# hex.net
KiCad netlist of a schematic drawn in Altium Designer
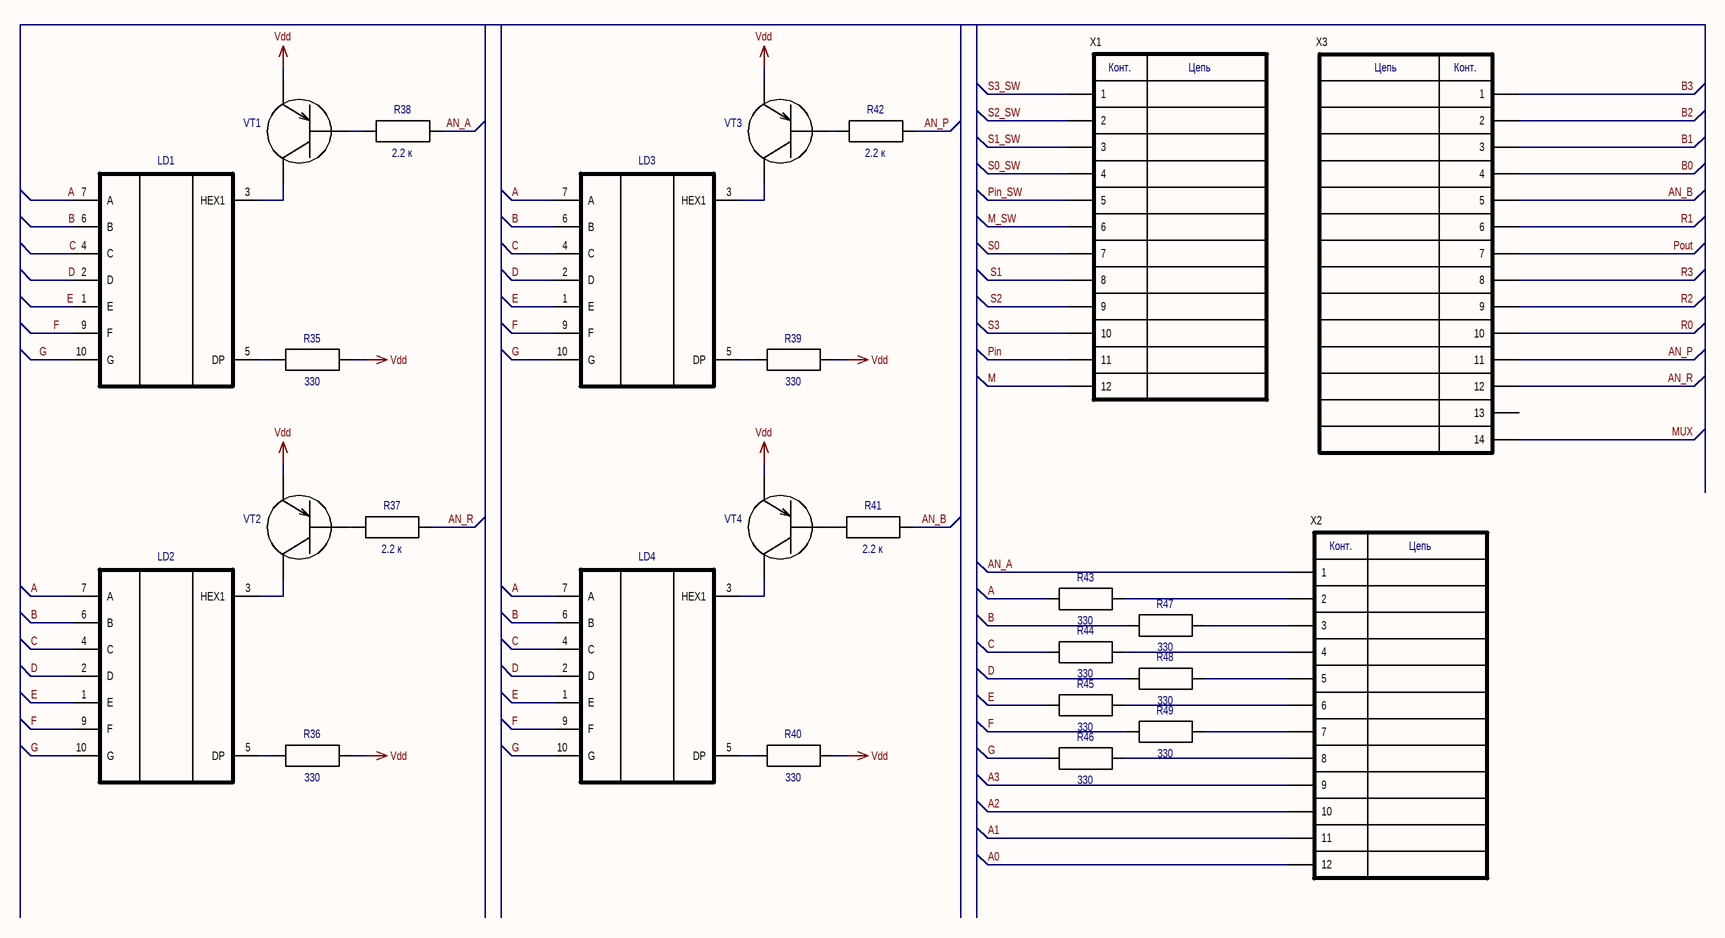
[diagram p0: hex.SchDoc]

(export (version "E")
  (design (tool "Eeschema 10.0.6"))
  (components
    (comp (ref "LD1")
      (value "4042AS (TSOT-23) Linear Technology")
      (footprint "HEX")
      (fields (field (name "PARTNUMBER") "4042AS"))
      (libsource (lib "ALU") (part "7-сегментный индикатор_2_1"))
    )
    (comp (ref "LD2")
      (value "4042AS (TSOT-23) Linear Technology")
      (footprint "HEX")
      (fields (field (name "PARTNUMBER") "4042AS"))
      (libsource (lib "ALU") (part "7-сегментный индикатор_2_1"))
    )
    (comp (ref "LD3")
      (value "4042AS (TSOT-23) Linear Technology")
      (footprint "HEX")
      (fields (field (name "PARTNUMBER") "4042AS"))
      (libsource (lib "ALU") (part "7-сегментный индикатор_2_1"))
    )
    (comp (ref "LD4")
      (value "4042AS (TSOT-23) Linear Technology")
      (footprint "HEX")
      (fields (field (name "PARTNUMBER") "4042AS"))
      (libsource (lib "ALU") (part "7-сегментный индикатор_2_1"))
    )
    (comp (ref "R35")
      (value "330")
      (footprint "P1-12-0.1(0603)")
      (fields (field (name "Comment") "330Ом ±* *, *"))
      (libsource (lib "Lisaveta") (part "R"))
    )
    (comp (ref "R36")
      (value "330")
      (footprint "P1-12-0.1(0603)")
      (fields (field (name "Comment") "330Ом ±* *, *"))
      (libsource (lib "Lisaveta") (part "R"))
    )
    (comp (ref "R37")
      (value "2.2 к")
      (footprint "P1-12-0.1(0603)")
      (fields (field (name "Comment") "2.2 кОм ±* *, *"))
      (libsource (lib "Lisaveta") (part "R"))
    )
    (comp (ref "R38")
      (value "2.2 к")
      (footprint "P1-12-0.1(0603)")
      (fields (field (name "Comment") "2.2 кОм ±* *, *"))
      (libsource (lib "Lisaveta") (part "R"))
    )
    (comp (ref "R39")
      (value "330")
      (footprint "P1-12-0.1(0603)")
      (fields (field (name "Comment") "330Ом ±* *, *"))
      (libsource (lib "Lisaveta") (part "R"))
    )
    (comp (ref "R40")
      (value "330")
      (footprint "P1-12-0.1(0603)")
      (fields (field (name "Comment") "330Ом ±* *, *"))
      (libsource (lib "Lisaveta") (part "R"))
    )
    (comp (ref "R41")
      (value "2.2 к")
      (footprint "P1-12-0.1(0603)")
      (fields (field (name "Comment") "2.2 кОм ±* *, *"))
      (libsource (lib "Lisaveta") (part "R"))
    )
    (comp (ref "R42")
      (value "2.2 к")
      (footprint "P1-12-0.1(0603)")
      (fields (field (name "Comment") "2.2 кОм ±* *, *"))
      (libsource (lib "Lisaveta") (part "R"))
    )
    (comp (ref "R43")
      (value "330")
      (footprint "P1-12-0.1(0603)")
      (fields (field (name "Comment") "330Ом ±* *, *"))
      (libsource (lib "Lisaveta") (part "R"))
    )
    (comp (ref "R44")
      (value "330")
      (footprint "P1-12-0.1(0603)")
      (fields (field (name "Comment") "330Ом ±* *, *"))
      (libsource (lib "Lisaveta") (part "R"))
    )
    (comp (ref "R45")
      (value "330")
      (footprint "P1-12-0.1(0603)")
      (fields (field (name "Comment") "330Ом ±* *, *"))
      (libsource (lib "Lisaveta") (part "R"))
    )
    (comp (ref "R46")
      (value "330")
      (footprint "P1-12-0.1(0603)")
      (fields (field (name "Comment") "330Ом ±* *, *"))
      (libsource (lib "Lisaveta") (part "R"))
    )
    (comp (ref "R47")
      (value "330")
      (footprint "P1-12-0.1(0603)")
      (fields (field (name "Comment") "330Ом ±* *, *"))
      (libsource (lib "Lisaveta") (part "R"))
    )
    (comp (ref "R48")
      (value "330")
      (footprint "P1-12-0.1(0603)")
      (fields (field (name "Comment") "330Ом ±* *, *"))
      (libsource (lib "Lisaveta") (part "R"))
    )
    (comp (ref "R49")
      (value "330")
      (footprint "P1-12-0.1(0603)")
      (fields (field (name "Comment") "330Ом ±* *, *"))
      (libsource (lib "Lisaveta") (part "R"))
    )
    (comp (ref "VT1")
      (value "BC857C (SOT-23) NXP")
      (footprint "SOT23(KT-46)")
      (fields (field (name "PARTNUMBER") "BC857C"))
      (libsource (lib "IVT_LIB") (part "VT - Биполярный транзистор PNP"))
    )
    (comp (ref "VT2")
      (value "BC857C (SOT-23) NXP")
      (footprint "SOT23(KT-46)")
      (fields (field (name "PARTNUMBER") "BC857C"))
      (libsource (lib "IVT_LIB") (part "VT - Биполярный транзистор PNP"))
    )
    (comp (ref "VT3")
      (value "BC857C (SOT-23) NXP")
      (footprint "SOT23(KT-46)")
      (fields (field (name "PARTNUMBER") "BC857C"))
      (libsource (lib "IVT_LIB") (part "VT - Биполярный транзистор PNP"))
    )
    (comp (ref "VT4")
      (value "BC857C (SOT-23) NXP")
      (footprint "SOT23(KT-46)")
      (fields (field (name "PARTNUMBER") "BC857C"))
      (libsource (lib "IVT_LIB") (part "VT - Биполярный транзистор PNP"))
    )
    (comp (ref "X1") (value "12pin") (footprint "PBD-12") (libsource (lib "ALU") (part "12pin")))
    (comp (ref "X2") (value "12pin") (footprint "PBD-12") (libsource (lib "ALU") (part "12pin")))
    (comp (ref "X3") (value "14pin") (footprint "PBD-14") (libsource (lib "ALU") (part "14pin")))
  )
  (nets
    (net (code "1") (name "/A") (class "Default")
      (node (ref "LD1") (pin "7") (pinfunction "A_7") (pintype "passive"))
      (node (ref "LD2") (pin "7") (pinfunction "A_7") (pintype "passive"))
      (node (ref "LD3") (pin "7") (pinfunction "A_7") (pintype "passive"))
      (node (ref "LD4") (pin "7") (pinfunction "A_7") (pintype "passive"))
      (node (ref "R43") (pin "1") (pinfunction "1_1") (pintype "passive"))
    )
    (net (code "2") (name "/A0") (class "Default")
      (node (ref "X2") (pin "12") (pinfunction "12_12") (pintype "passive"))
    )
    (net (code "3") (name "/A1") (class "Default")
      (node (ref "X2") (pin "11") (pinfunction "11_11") (pintype "passive"))
    )
    (net (code "4") (name "/A2") (class "Default")
      (node (ref "X2") (pin "10") (pinfunction "10_10") (pintype "passive"))
    )
    (net (code "5") (name "/A3") (class "Default")
      (node (ref "X2") (pin "9") (pinfunction "9_9") (pintype "passive"))
    )
    (net (code "6") (name "/AN_A") (class "Default")
      (node (ref "R38") (pin "2") (pinfunction "2_2") (pintype "passive"))
      (node (ref "X2") (pin "1") (pinfunction "1_1") (pintype "passive"))
    )
    (net (code "7") (name "/AN_B") (class "Default")
      (node (ref "R41") (pin "2") (pinfunction "2_2") (pintype "passive"))
      (node (ref "X3") (pin "5") (pinfunction "5_5") (pintype "passive"))
    )
    (net (code "8") (name "/AN_P") (class "Default")
      (node (ref "R42") (pin "2") (pinfunction "2_2") (pintype "passive"))
      (node (ref "X3") (pin "11") (pinfunction "11_11") (pintype "passive"))
    )
    (net (code "9") (name "/AN_R") (class "Default")
      (node (ref "R37") (pin "2") (pinfunction "2_2") (pintype "passive"))
      (node (ref "X3") (pin "12") (pinfunction "12_12") (pintype "passive"))
    )
    (net (code "10") (name "/B") (class "Default")
      (node (ref "LD1") (pin "6") (pinfunction "B_6") (pintype "passive"))
      (node (ref "LD2") (pin "6") (pinfunction "B_6") (pintype "passive"))
      (node (ref "LD3") (pin "6") (pinfunction "B_6") (pintype "passive"))
      (node (ref "LD4") (pin "6") (pinfunction "B_6") (pintype "passive"))
      (node (ref "R47") (pin "1") (pinfunction "1_1") (pintype "passive"))
    )
    (net (code "11") (name "/B0") (class "Default")
      (node (ref "X3") (pin "4") (pinfunction "4_4") (pintype "passive"))
    )
    (net (code "12") (name "/B1") (class "Default")
      (node (ref "X3") (pin "3") (pinfunction "3_3") (pintype "passive"))
    )
    (net (code "13") (name "/B2") (class "Default")
      (node (ref "X3") (pin "2") (pinfunction "2_2") (pintype "passive"))
    )
    (net (code "14") (name "/B3") (class "Default")
      (node (ref "X3") (pin "1") (pinfunction "1_1") (pintype "passive"))
    )
    (net (code "15") (name "/C") (class "Default")
      (node (ref "LD1") (pin "4") (pinfunction "C_4") (pintype "passive"))
      (node (ref "LD2") (pin "4") (pinfunction "C_4") (pintype "passive"))
      (node (ref "LD3") (pin "4") (pinfunction "C_4") (pintype "passive"))
      (node (ref "LD4") (pin "4") (pinfunction "C_4") (pintype "passive"))
      (node (ref "R44") (pin "1") (pinfunction "1_1") (pintype "passive"))
    )
    (net (code "16") (name "/D") (class "Default")
      (node (ref "LD1") (pin "2") (pinfunction "D_2") (pintype "passive"))
      (node (ref "LD2") (pin "2") (pinfunction "D_2") (pintype "passive"))
      (node (ref "LD3") (pin "2") (pinfunction "D_2") (pintype "passive"))
      (node (ref "LD4") (pin "2") (pinfunction "D_2") (pintype "passive"))
      (node (ref "R48") (pin "1") (pinfunction "1_1") (pintype "passive"))
    )
    (net (code "17") (name "/E") (class "Default")
      (node (ref "LD1") (pin "1") (pinfunction "E_1") (pintype "passive"))
      (node (ref "LD2") (pin "1") (pinfunction "E_1") (pintype "passive"))
      (node (ref "LD3") (pin "1") (pinfunction "E_1") (pintype "passive"))
      (node (ref "LD4") (pin "1") (pinfunction "E_1") (pintype "passive"))
      (node (ref "R45") (pin "1") (pinfunction "1_1") (pintype "passive"))
    )
    (net (code "18") (name "/F") (class "Default")
      (node (ref "LD1") (pin "9") (pinfunction "F_9") (pintype "passive"))
      (node (ref "LD2") (pin "9") (pinfunction "F_9") (pintype "passive"))
      (node (ref "LD3") (pin "9") (pinfunction "F_9") (pintype "passive"))
      (node (ref "LD4") (pin "9") (pinfunction "F_9") (pintype "passive"))
      (node (ref "R49") (pin "1") (pinfunction "1_1") (pintype "passive"))
    )
    (net (code "19") (name "/G") (class "Default")
      (node (ref "LD1") (pin "10") (pinfunction "G_10") (pintype "passive"))
      (node (ref "LD2") (pin "10") (pinfunction "G_10") (pintype "passive"))
      (node (ref "LD3") (pin "10") (pinfunction "G_10") (pintype "passive"))
      (node (ref "LD4") (pin "10") (pinfunction "G_10") (pintype "passive"))
      (node (ref "R46") (pin "1") (pinfunction "1_1") (pintype "passive"))
    )
    (net (code "20") (name "/M") (class "Default")
      (node (ref "X1") (pin "12") (pinfunction "12_12") (pintype "passive"))
    )
    (net (code "21") (name "/MUX") (class "Default")
      (node (ref "X3") (pin "14") (pinfunction "14_14") (pintype "passive"))
    )
    (net (code "22") (name "/M_SW") (class "Default")
      (node (ref "X1") (pin "6") (pinfunction "6_6") (pintype "passive"))
    )
    (net (code "23") (name "/Pin") (class "Default")
      (node (ref "X1") (pin "11") (pinfunction "11_11") (pintype "passive"))
    )
    (net (code "24") (name "/Pin_SW") (class "Default")
      (node (ref "X1") (pin "5") (pinfunction "5_5") (pintype "passive"))
    )
    (net (code "25") (name "/Pout") (class "Default")
      (node (ref "X3") (pin "7") (pinfunction "7_7") (pintype "passive"))
    )
    (net (code "26") (name "/R0") (class "Default")
      (node (ref "X3") (pin "10") (pinfunction "10_10") (pintype "passive"))
    )
    (net (code "27") (name "/R1") (class "Default")
      (node (ref "X3") (pin "6") (pinfunction "6_6") (pintype "passive"))
    )
    (net (code "28") (name "/R2") (class "Default")
      (node (ref "X3") (pin "9") (pinfunction "9_9") (pintype "passive"))
    )
    (net (code "29") (name "/R3") (class "Default")
      (node (ref "X3") (pin "8") (pinfunction "8_8") (pintype "passive"))
    )
    (net (code "30") (name "/S0") (class "Default")
      (node (ref "X1") (pin "7") (pinfunction "7_7") (pintype "passive"))
    )
    (net (code "31") (name "/S0_SW") (class "Default")
      (node (ref "X1") (pin "4") (pinfunction "4_4") (pintype "passive"))
    )
    (net (code "32") (name "/S1") (class "Default")
      (node (ref "X1") (pin "8") (pinfunction "8_8") (pintype "passive"))
    )
    (net (code "33") (name "/S1_SW") (class "Default")
      (node (ref "X1") (pin "3") (pinfunction "3_3") (pintype "passive"))
    )
    (net (code "34") (name "/S2") (class "Default")
      (node (ref "X1") (pin "9") (pinfunction "9_9") (pintype "passive"))
    )
    (net (code "35") (name "/S2_SW") (class "Default")
      (node (ref "X1") (pin "2") (pinfunction "2_2") (pintype "passive"))
    )
    (net (code "36") (name "/S3") (class "Default")
      (node (ref "X1") (pin "10") (pinfunction "10_10") (pintype "passive"))
    )
    (net (code "37") (name "/S3_SW") (class "Default")
      (node (ref "X1") (pin "1") (pinfunction "1_1") (pintype "passive"))
    )
    (net (code "38") (name "Net-(LD1-DP)") (class "Default")
      (node (ref "LD1") (pin "5") (pinfunction "DP_5") (pintype "passive"))
      (node (ref "R35") (pin "1") (pinfunction "1_1") (pintype "passive"))
    )
    (net (code "39") (name "Net-(LD1-HEX1)") (class "Default")
      (node (ref "LD1") (pin "3") (pinfunction "HEX1_3") (pintype "passive"))
      (node (ref "VT1") (pin "3") (pinfunction "3_3") (pintype "passive"))
    )
    (net (code "40") (name "Net-(LD2-DP)") (class "Default")
      (node (ref "LD2") (pin "5") (pinfunction "DP_5") (pintype "passive"))
      (node (ref "R36") (pin "1") (pinfunction "1_1") (pintype "passive"))
    )
    (net (code "41") (name "Net-(LD2-HEX1)") (class "Default")
      (node (ref "LD2") (pin "3") (pinfunction "HEX1_3") (pintype "passive"))
      (node (ref "VT2") (pin "3") (pinfunction "3_3") (pintype "passive"))
    )
    (net (code "42") (name "Net-(LD3-DP)") (class "Default")
      (node (ref "LD3") (pin "5") (pinfunction "DP_5") (pintype "passive"))
      (node (ref "R39") (pin "1") (pinfunction "1_1") (pintype "passive"))
    )
    (net (code "43") (name "Net-(LD3-HEX1)") (class "Default")
      (node (ref "LD3") (pin "3") (pinfunction "HEX1_3") (pintype "passive"))
      (node (ref "VT3") (pin "3") (pinfunction "3_3") (pintype "passive"))
    )
    (net (code "44") (name "Net-(LD4-DP)") (class "Default")
      (node (ref "LD4") (pin "5") (pinfunction "DP_5") (pintype "passive"))
      (node (ref "R40") (pin "1") (pinfunction "1_1") (pintype "passive"))
    )
    (net (code "45") (name "Net-(LD4-HEX1)") (class "Default")
      (node (ref "LD4") (pin "3") (pinfunction "HEX1_3") (pintype "passive"))
      (node (ref "VT4") (pin "3") (pinfunction "3_3") (pintype "passive"))
    )
    (net (code "46") (name "Net-(R37-Pad1)") (class "Default")
      (node (ref "R37") (pin "1") (pinfunction "1_1") (pintype "passive"))
      (node (ref "VT2") (pin "1") (pinfunction "1_1") (pintype "passive"))
    )
    (net (code "47") (name "Net-(R38-Pad1)") (class "Default")
      (node (ref "R38") (pin "1") (pinfunction "1_1") (pintype "passive"))
      (node (ref "VT1") (pin "1") (pinfunction "1_1") (pintype "passive"))
    )
    (net (code "48") (name "Net-(R41-Pad1)") (class "Default")
      (node (ref "R41") (pin "1") (pinfunction "1_1") (pintype "passive"))
      (node (ref "VT4") (pin "1") (pinfunction "1_1") (pintype "passive"))
    )
    (net (code "49") (name "Net-(R42-Pad1)") (class "Default")
      (node (ref "R42") (pin "1") (pinfunction "1_1") (pintype "passive"))
      (node (ref "VT3") (pin "1") (pinfunction "1_1") (pintype "passive"))
    )
    (net (code "50") (name "Net-(R43-Pad2)") (class "Default")
      (node (ref "R43") (pin "2") (pinfunction "2_2") (pintype "passive"))
      (node (ref "X2") (pin "2") (pinfunction "2_2") (pintype "passive"))
    )
    (net (code "51") (name "Net-(R44-Pad2)") (class "Default")
      (node (ref "R44") (pin "2") (pinfunction "2_2") (pintype "passive"))
      (node (ref "X2") (pin "4") (pinfunction "4_4") (pintype "passive"))
    )
    (net (code "52") (name "Net-(R45-Pad2)") (class "Default")
      (node (ref "R45") (pin "2") (pinfunction "2_2") (pintype "passive"))
      (node (ref "X2") (pin "6") (pinfunction "6_6") (pintype "passive"))
    )
    (net (code "53") (name "Net-(R46-Pad2)") (class "Default")
      (node (ref "R46") (pin "2") (pinfunction "2_2") (pintype "passive"))
      (node (ref "X2") (pin "8") (pinfunction "8_8") (pintype "passive"))
    )
    (net (code "54") (name "Net-(R47-Pad2)") (class "Default")
      (node (ref "R47") (pin "2") (pinfunction "2_2") (pintype "passive"))
      (node (ref "X2") (pin "3") (pinfunction "3_3") (pintype "passive"))
    )
    (net (code "55") (name "Net-(R48-Pad2)") (class "Default")
      (node (ref "R48") (pin "2") (pinfunction "2_2") (pintype "passive"))
      (node (ref "X2") (pin "5") (pinfunction "5_5") (pintype "passive"))
    )
    (net (code "56") (name "Net-(R49-Pad2)") (class "Default")
      (node (ref "R49") (pin "2") (pinfunction "2_2") (pintype "passive"))
      (node (ref "X2") (pin "7") (pinfunction "7_7") (pintype "passive"))
    )
    (net (code "57") (name "Vdd") (class "Default")
      (node (ref "R35") (pin "2") (pinfunction "2_2") (pintype "passive"))
      (node (ref "R36") (pin "2") (pinfunction "2_2") (pintype "passive"))
      (node (ref "R39") (pin "2") (pinfunction "2_2") (pintype "passive"))
      (node (ref "R40") (pin "2") (pinfunction "2_2") (pintype "passive"))
      (node (ref "VT1") (pin "2") (pinfunction "2_2") (pintype "passive"))
      (node (ref "VT2") (pin "2") (pinfunction "2_2") (pintype "passive"))
      (node (ref "VT3") (pin "2") (pinfunction "2_2") (pintype "passive"))
      (node (ref "VT4") (pin "2") (pinfunction "2_2") (pintype "passive"))
    )
    (net (code "58") (name "unconnected-(X3-Pad13)") (class "Default")
      (node (ref "X3") (pin "13") (pinfunction "13_13") (pintype "passive"))
    )
  )
)
